# mainbrd.net
KiCad netlist of a schematic drawn in EAGLE
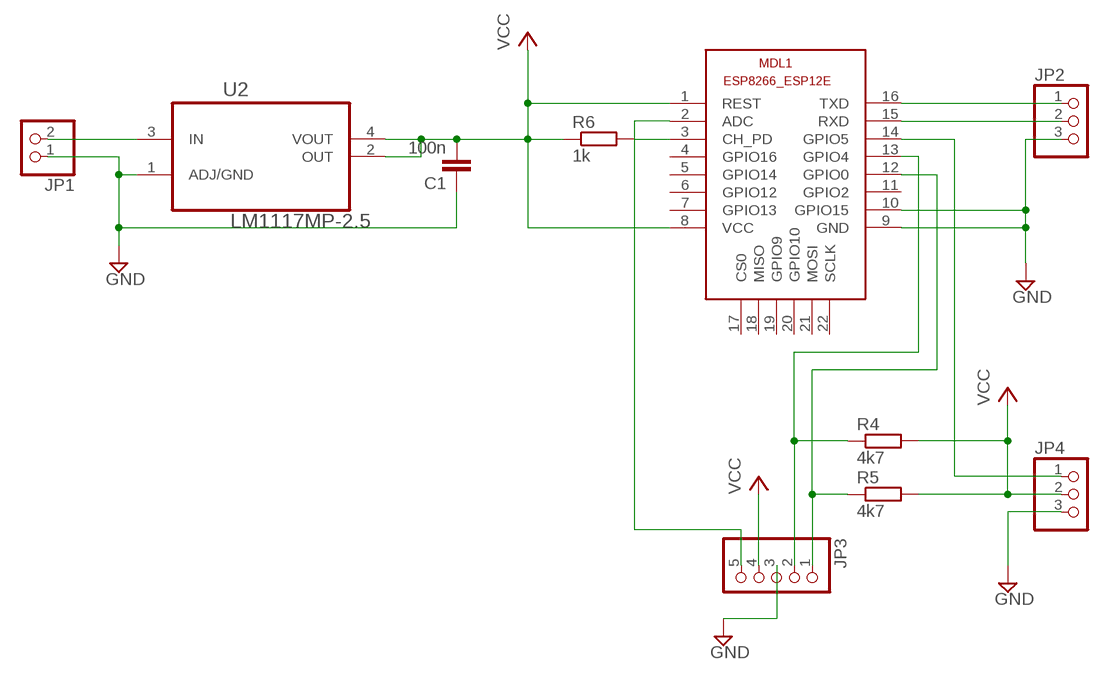
[diagram p0: schematic, sheet 1]

(export (version "E")
  (design (tool "Eeschema 10.0.6"))
  (components
    (comp (ref "C1")
      (value "100n")
      (footprint "eagle-import:C0805")
      (libsource (lib "eagle-import") (part "C-EUC0805"))
    )
    (comp (ref "JP1")
      (value "PINHD-1X2")
      (footprint "eagle-import:1X02")
      (libsource (lib "eagle-import") (part "PINHD-1X2"))
    )
    (comp (ref "JP2")
      (value "PINHD-1X3")
      (footprint "eagle-import:1X03")
      (libsource (lib "eagle-import") (part "PINHD-1X3"))
    )
    (comp (ref "JP3")
      (value "PINHD-1X5")
      (footprint "eagle-import:1X05")
      (libsource (lib "eagle-import") (part "PINHD-1X5"))
    )
    (comp (ref "JP4")
      (value "PINHD-1X3")
      (footprint "eagle-import:1X03")
      (libsource (lib "eagle-import") (part "PINHD-1X3"))
    )
    (comp (ref "MDL1")
      (value "ESP8266-12EESP8266-ESP12E")
      (footprint "eagle-import:ESP8266-ESP12E")
      (libsource (lib "eagle-import") (part "ESP8266-12EESP8266-ESP12E"))
    )
    (comp (ref "R4")
      (value "4k7")
      (footprint "eagle-import:R0805")
      (libsource (lib "eagle-import") (part "R-EU_R0805"))
    )
    (comp (ref "R5")
      (value "4k7")
      (footprint "eagle-import:R0805")
      (libsource (lib "eagle-import") (part "R-EU_R0805"))
    )
    (comp (ref "R6")
      (value "1k")
      (footprint "eagle-import:R0805")
      (libsource (lib "eagle-import") (part "R-EU_R0805"))
    )
    (comp (ref "U2")
      (value "LM1117MP-2.5")
      (footprint "eagle-import:SOT230P696X180-4N")
      (libsource (lib "eagle-import") (part "LM1117MP-2.5"))
    )
  )
  (nets
    (net (code "1") (name "GND") (class "Default")
      (node (ref "C1") (pin "1") (pinfunction "1_1") (pintype "passive"))
      (node (ref "JP1") (pin "1") (pinfunction "1_1") (pintype "passive"))
      (node (ref "JP2") (pin "3") (pinfunction "3_3") (pintype "passive"))
      (node (ref "JP3") (pin "3") (pinfunction "3_3") (pintype "passive"))
      (node (ref "JP4") (pin "3") (pinfunction "3_3") (pintype "passive"))
      (node (ref "MDL1") (pin "10") (pinfunction "GPIO15_10") (pintype "bidirectional"))
      (node (ref "MDL1") (pin "9") (pinfunction "GND_9") (pintype "bidirectional"))
      (node (ref "U2") (pin "1") (pinfunction "ADJ/GND_1") (pintype "passive"))
    )
    (net (code "2") (name "Net-(MDL1-ADC)") (class "Default")
      (node (ref "JP3") (pin "5") (pinfunction "5_5") (pintype "passive"))
      (node (ref "MDL1") (pin "2") (pinfunction "ADC_2") (pintype "bidirectional"))
    )
    (net (code "3") (name "Net-(MDL1-CH_PD)") (class "Default")
      (node (ref "MDL1") (pin "3") (pinfunction "CH_PD_3") (pintype "bidirectional"))
      (node (ref "R6") (pin "2") (pinfunction "2_2") (pintype "passive"))
    )
    (net (code "4") (name "Net-(MDL1-GPIO0)") (class "Default")
      (node (ref "JP3") (pin "1") (pinfunction "1_1") (pintype "passive"))
      (node (ref "MDL1") (pin "12") (pinfunction "GPIO0_12") (pintype "bidirectional"))
      (node (ref "R5") (pin "1") (pinfunction "1_1") (pintype "passive"))
    )
    (net (code "5") (name "Net-(MDL1-GPIO4)") (class "Default")
      (node (ref "JP3") (pin "2") (pinfunction "2_2") (pintype "passive"))
      (node (ref "MDL1") (pin "13") (pinfunction "GPIO4_13") (pintype "bidirectional"))
      (node (ref "R4") (pin "1") (pinfunction "1_1") (pintype "passive"))
    )
    (net (code "6") (name "Net-(MDL1-GPIO5)") (class "Default")
      (node (ref "JP4") (pin "1") (pinfunction "1_1") (pintype "passive"))
      (node (ref "MDL1") (pin "14") (pinfunction "GPIO5_14") (pintype "bidirectional"))
    )
    (net (code "7") (name "Net-(MDL1-RXD)") (class "Default")
      (node (ref "JP2") (pin "2") (pinfunction "2_2") (pintype "passive"))
      (node (ref "MDL1") (pin "15") (pinfunction "RXD_15") (pintype "bidirectional"))
    )
    (net (code "8") (name "Net-(MDL1-TXD)") (class "Default")
      (node (ref "JP2") (pin "1") (pinfunction "1_1") (pintype "passive"))
      (node (ref "MDL1") (pin "16") (pinfunction "TXD_16") (pintype "bidirectional"))
    )
    (net (code "9") (name "Net-(U2-IN)") (class "Default")
      (node (ref "JP1") (pin "2") (pinfunction "2_2") (pintype "passive"))
      (node (ref "U2") (pin "3") (pinfunction "IN_3") (pintype "input"))
    )
    (net (code "10") (name "VCC") (class "Default")
      (node (ref "C1") (pin "2") (pinfunction "2_2") (pintype "passive"))
      (node (ref "JP3") (pin "4") (pinfunction "4_4") (pintype "passive"))
      (node (ref "JP4") (pin "2") (pinfunction "2_2") (pintype "passive"))
      (node (ref "MDL1") (pin "1") (pinfunction "REST_1") (pintype "bidirectional"))
      (node (ref "MDL1") (pin "8") (pinfunction "VCC_8") (pintype "bidirectional"))
      (node (ref "R4") (pin "2") (pinfunction "2_2") (pintype "passive"))
      (node (ref "R5") (pin "2") (pinfunction "2_2") (pintype "passive"))
      (node (ref "R6") (pin "1") (pinfunction "1_1") (pintype "passive"))
      (node (ref "U2") (pin "2") (pinfunction "OUT_2") (pintype "output"))
      (node (ref "U2") (pin "4") (pinfunction "VOUT_4") (pintype "output"))
    )
    (net (code "11") (name "unconnected-(MDL1-CS0-Pad17)") (class "Default")
      (node (ref "MDL1") (pin "17") (pinfunction "CS0_17") (pintype "bidirectional"))
    )
    (net (code "12") (name "unconnected-(MDL1-GPIO2-Pad11)") (class "Default")
      (node (ref "MDL1") (pin "11") (pinfunction "GPIO2_11") (pintype "bidirectional"))
    )
    (net (code "13") (name "unconnected-(MDL1-GPIO9-Pad19)") (class "Default")
      (node (ref "MDL1") (pin "19") (pinfunction "GPIO9_19") (pintype "bidirectional"))
    )
    (net (code "14") (name "unconnected-(MDL1-GPIO10-Pad20)") (class "Default")
      (node (ref "MDL1") (pin "20") (pinfunction "GPIO10_20") (pintype "bidirectional"))
    )
    (net (code "15") (name "unconnected-(MDL1-GPIO12-Pad6)") (class "Default")
      (node (ref "MDL1") (pin "6") (pinfunction "GPIO12_6") (pintype "bidirectional"))
    )
    (net (code "16") (name "unconnected-(MDL1-GPIO13-Pad7)") (class "Default")
      (node (ref "MDL1") (pin "7") (pinfunction "GPIO13_7") (pintype "bidirectional"))
    )
    (net (code "17") (name "unconnected-(MDL1-GPIO14-Pad5)") (class "Default")
      (node (ref "MDL1") (pin "5") (pinfunction "GPIO14_5") (pintype "bidirectional"))
    )
    (net (code "18") (name "unconnected-(MDL1-GPIO16-Pad4)") (class "Default")
      (node (ref "MDL1") (pin "4") (pinfunction "GPIO16_4") (pintype "bidirectional"))
    )
    (net (code "19") (name "unconnected-(MDL1-MISO-Pad18)") (class "Default")
      (node (ref "MDL1") (pin "18") (pinfunction "MISO_18") (pintype "bidirectional"))
    )
    (net (code "20") (name "unconnected-(MDL1-MOSI-Pad21)") (class "Default")
      (node (ref "MDL1") (pin "21") (pinfunction "MOSI_21") (pintype "bidirectional"))
    )
    (net (code "21") (name "unconnected-(MDL1-SCLK-Pad22)") (class "Default")
      (node (ref "MDL1") (pin "22") (pinfunction "SCLK_22") (pintype "bidirectional"))
    )
  )
)
